# PLL.net
KiCad netlist of a schematic drawn in Altium Designer
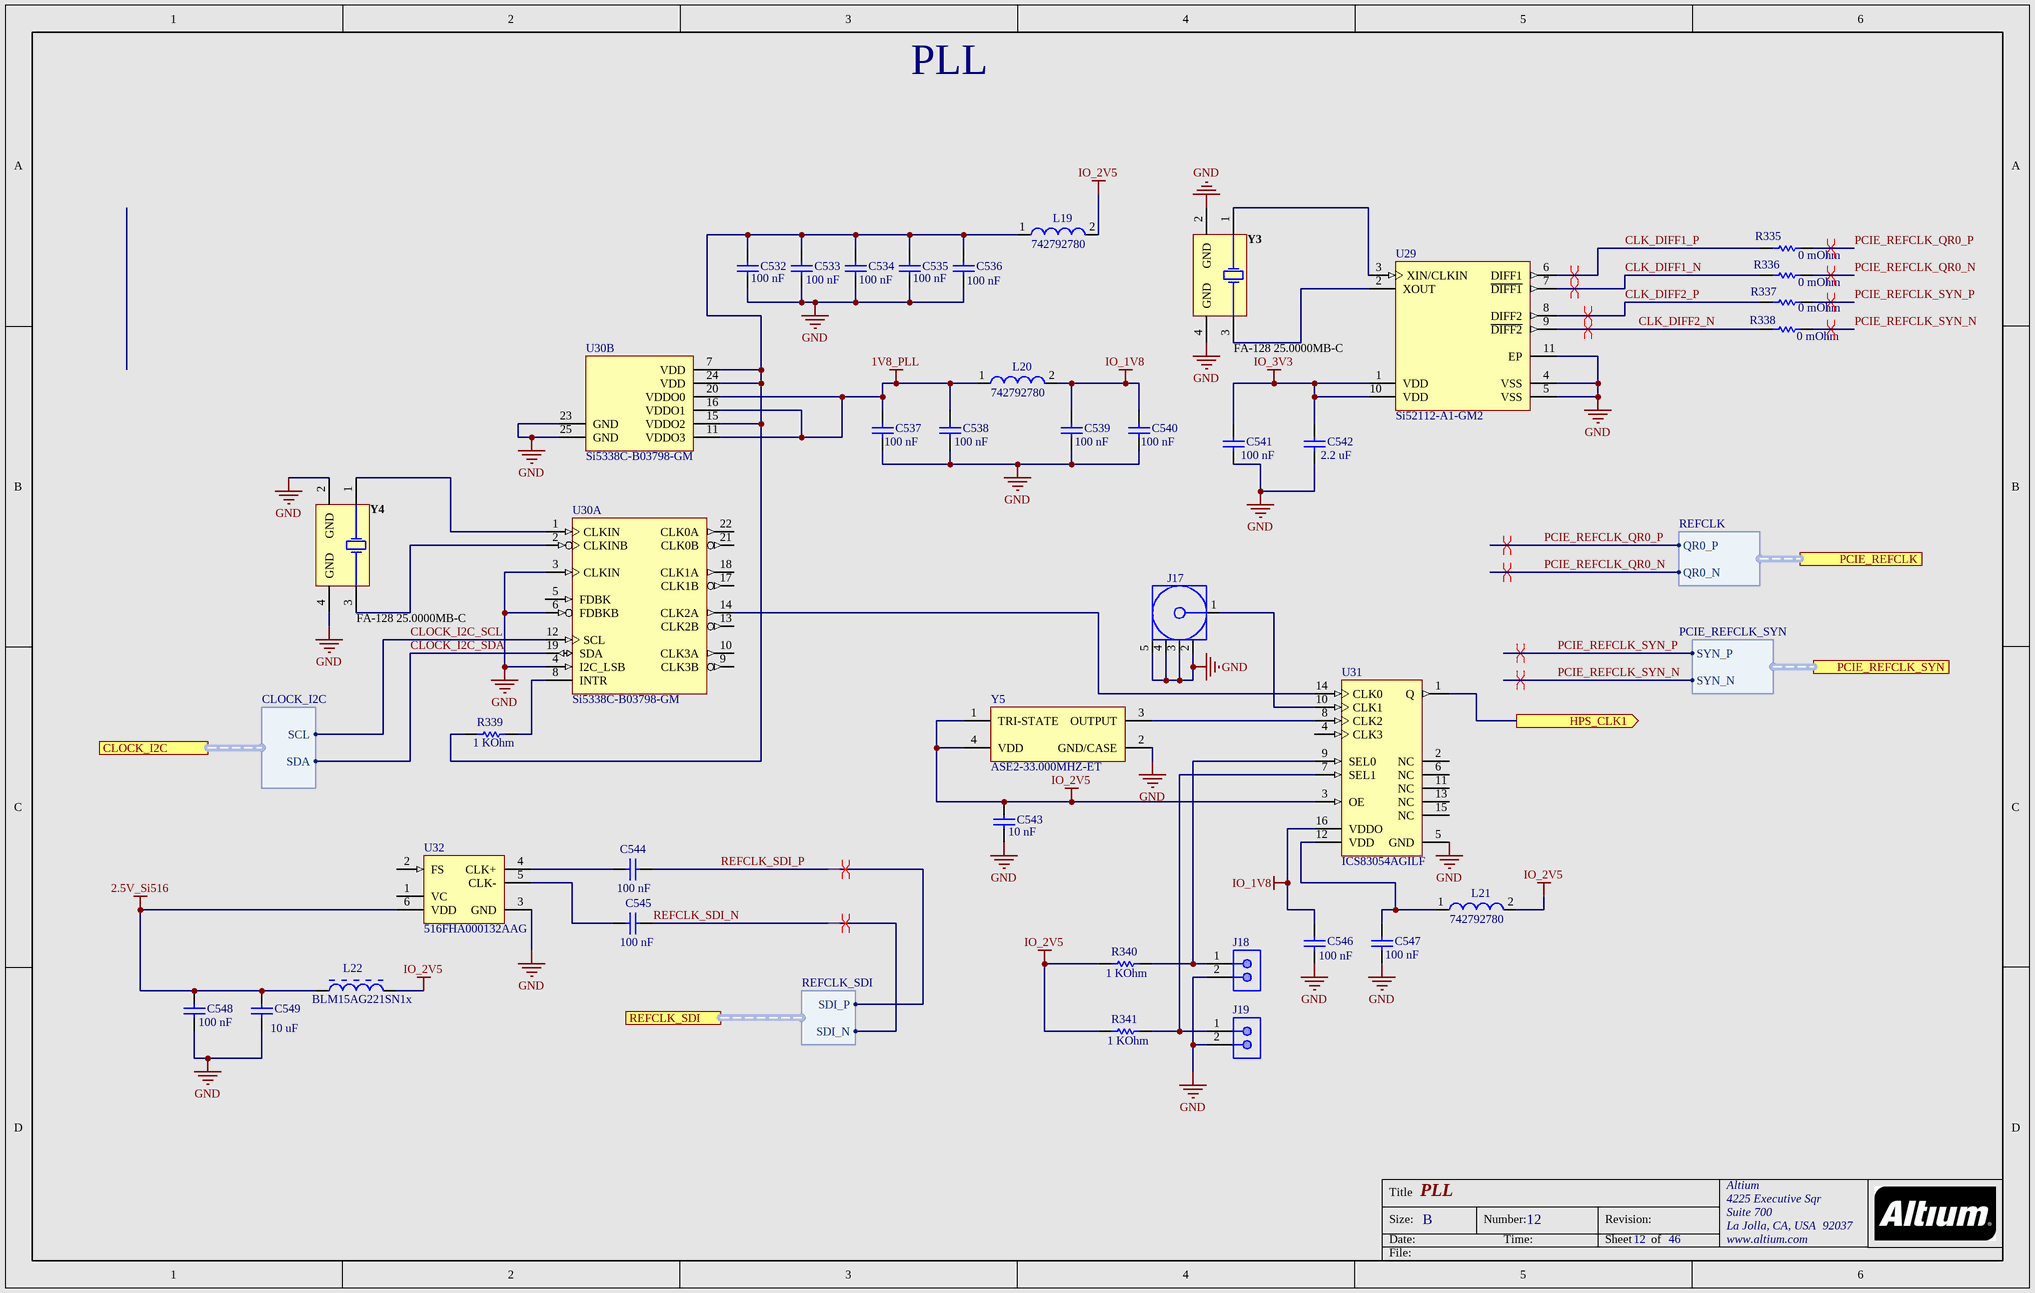
[diagram p0: PLL.SchDoc]

(export (version "E")
  (design (tool "Eeschema 10.0.6"))
  (components
    (comp (ref "C532")
      (value "C1005X7R1E104M")
      (footprint "CAPC1005X55X10LL05")
      (description "Chip Capacitor, 0.1 uF, +/- 20%, 25 V, -55 to 125 degC, 0402 (1005 Metric), RoHS, Tape and Reel")
      (fields (field (name "TOLERANCE") "20%") (field (name "CAPACITANCE") "100 nF"))
      (libsource (lib "Altium Content Vault") (part "CAP-NP-2"))
    )
    (comp (ref "C533")
      (value "C1005X7R1E104M")
      (footprint "CAPC1005X55X10LL05")
      (description "Chip Capacitor, 0.1 uF, +/- 20%, 25 V, -55 to 125 degC, 0402 (1005 Metric), RoHS, Tape and Reel")
      (fields (field (name "TOLERANCE") "20%") (field (name "CAPACITANCE") "100 nF"))
      (libsource (lib "Altium Content Vault") (part "CAP-NP-2"))
    )
    (comp (ref "C534")
      (value "C1005X7R1E104M")
      (footprint "CAPC1005X55X10LL05")
      (description "Chip Capacitor, 0.1 uF, +/- 20%, 25 V, -55 to 125 degC, 0402 (1005 Metric), RoHS, Tape and Reel")
      (fields (field (name "TOLERANCE") "20%") (field (name "CAPACITANCE") "100 nF"))
      (libsource (lib "Altium Content Vault") (part "CAP-NP-2"))
    )
    (comp (ref "C535")
      (value "C1005X7R1E104M")
      (footprint "CAPC1005X55X10LL05")
      (description "Chip Capacitor, 0.1 uF, +/- 20%, 25 V, -55 to 125 degC, 0402 (1005 Metric), RoHS, Tape and Reel")
      (fields (field (name "TOLERANCE") "20%") (field (name "CAPACITANCE") "100 nF"))
      (libsource (lib "Altium Content Vault") (part "CAP-NP-2"))
    )
    (comp (ref "C536")
      (value "C1005X7R1E104M")
      (footprint "CAPC1005X55X10LL05")
      (description "Chip Capacitor, 0.1 uF, +/- 20%, 25 V, -55 to 125 degC, 0402 (1005 Metric), RoHS, Tape and Reel")
      (fields (field (name "TOLERANCE") "20%") (field (name "CAPACITANCE") "100 nF"))
      (libsource (lib "Altium Content Vault") (part "CAP-NP-2"))
    )
    (comp (ref "C537")
      (value "C1005X7R1E104M")
      (footprint "CAPC1005X55X10LL05")
      (description "Chip Capacitor, 0.1 uF, +/- 20%, 25 V, -55 to 125 degC, 0402 (1005 Metric), RoHS, Tape and Reel")
      (fields (field (name "TOLERANCE") "20%") (field (name "CAPACITANCE") "100 nF"))
      (libsource (lib "Altium Content Vault") (part "CAP-NP-2"))
    )
    (comp (ref "C538")
      (value "C1005X7R1E104M")
      (footprint "CAPC1005X55X10LL05")
      (description "Chip Capacitor, 0.1 uF, +/- 20%, 25 V, -55 to 125 degC, 0402 (1005 Metric), RoHS, Tape and Reel")
      (fields (field (name "TOLERANCE") "20%") (field (name "CAPACITANCE") "100 nF"))
      (libsource (lib "Altium Content Vault") (part "CAP-NP-2"))
    )
    (comp (ref "C539")
      (value "C1005X7R1E104M")
      (footprint "CAPC1005X55X10LL05")
      (description "Chip Capacitor, 0.1 uF, +/- 20%, 25 V, -55 to 125 degC, 0402 (1005 Metric), RoHS, Tape and Reel")
      (fields (field (name "TOLERANCE") "20%") (field (name "CAPACITANCE") "100 nF"))
      (libsource (lib "Altium Content Vault") (part "CAP-NP-2"))
    )
    (comp (ref "C540")
      (value "C1005X7R1E104M")
      (footprint "CAPC1005X55X10LL05")
      (description "Chip Capacitor, 0.1 uF, +/- 20%, 25 V, -55 to 125 degC, 0402 (1005 Metric), RoHS, Tape and Reel")
      (fields (field (name "TOLERANCE") "20%") (field (name "CAPACITANCE") "100 nF"))
      (libsource (lib "Altium Content Vault") (part "CAP-NP-2"))
    )
    (comp (ref "C541")
      (value "C1005X7R1E104M")
      (footprint "CAPC1005X55X10LL05")
      (description "Chip Capacitor, 0.1 uF, +/- 20%, 25 V, -55 to 125 degC, 0402 (1005 Metric), RoHS, Tape and Reel")
      (fields (field (name "TOLERANCE") "20%") (field (name "CAPACITANCE") "100 nF"))
      (libsource (lib "Altium Content Vault") (part "CAP-NP-2"))
    )
    (comp (ref "C542")
      (value "GRM188R61A225KE34x")
      (footprint "CAPC1608X90X35ML10T15")
      (description "Chip Capacitor, 2.2 uF, +/- 10%, 10 V, -55 to 85 degC, 0603 (1608 Metric), RoHS, Tape and Reel")
      (fields (field (name "TOLERANCE") "10%") (field (name "CAPACITANCE") "2.2 uF"))
      (libsource (lib "") (part "CAP-NP-2_1"))
    )
    (comp (ref "C543")
      (value "GRM155R71H103KA88D")
      (footprint "CAPC1005X55X25ML05T10")
      (description "Chip Capacitor, 10 nF, +/- 10%, 50 V, -55 to 125 degC, 0402 (1005 Metric), RoHS, Tape and Reel")
      (fields
        (field (name "TOLERANCE") "10%")
        (field (name "CAPACITANCE") "10 nF")
        (field (name "MANUFACTURER") "Basic Passives")
      )
      (libsource (lib "Altium Content Vault") (part "CAP-NP-2"))
    )
    (comp (ref "C544")
      (value "C1005X7R1E104M")
      (footprint "CAPC1005X55X10LL05")
      (description "Chip Capacitor, 0.1 uF, +/- 20%, 25 V, -55 to 125 degC, 0402 (1005 Metric), RoHS, Tape and Reel")
      (fields (field (name "TOLERANCE") "20%") (field (name "CAPACITANCE") "100 nF"))
      (libsource (lib "Altium Content Vault") (part "CAP-NP-2"))
    )
    (comp (ref "C545")
      (value "C1005X7R1E104M")
      (footprint "CAPC1005X55X10LL05")
      (description "Chip Capacitor, 0.1 uF, +/- 20%, 25 V, -55 to 125 degC, 0402 (1005 Metric), RoHS, Tape and Reel")
      (fields (field (name "TOLERANCE") "20%") (field (name "CAPACITANCE") "100 nF"))
      (libsource (lib "Altium Content Vault") (part "CAP-NP-2"))
    )
    (comp (ref "C546")
      (value "C1005X7R1E104M")
      (footprint "CAPC1005X55X10LL05")
      (description "Chip Capacitor, 0.1 uF, +/- 20%, 25 V, -55 to 125 degC, 0402 (1005 Metric), RoHS, Tape and Reel")
      (fields (field (name "TOLERANCE") "20%") (field (name "CAPACITANCE") "100 nF"))
      (libsource (lib "Altium Content Vault") (part "CAP-NP-2"))
    )
    (comp (ref "C547")
      (value "C1005X7R1E104M")
      (footprint "CAPC1005X55X10LL05")
      (description "Chip Capacitor, 0.1 uF, +/- 20%, 25 V, -55 to 125 degC, 0402 (1005 Metric), RoHS, Tape and Reel")
      (fields (field (name "TOLERANCE") "20%") (field (name "CAPACITANCE") "100 nF"))
      (libsource (lib "Altium Content Vault") (part "CAP-NP-2"))
    )
    (comp (ref "C548")
      (value "C1005X7R1E104M")
      (footprint "CAPC1005X55X10LL05")
      (description "Chip Capacitor, 0.1 uF, +/- 20%, 25 V, -55 to 125 degC, 0402 (1005 Metric), RoHS, Tape and Reel")
      (fields (field (name "TOLERANCE") "20%") (field (name "CAPACITANCE") "100 nF"))
      (libsource (lib "Altium Content Vault") (part "CAP-NP-2"))
    )
    (comp (ref "C549")
      (value "C2012X5R1C106K085AC")
      (footprint "CAPC2013X100X20NL20")
      (description "Chip Capacitor, 10 uF, +/- 10%, 16 V, -55 to 85 degC, 0805 (2012 Metric), RoHS, Tape and Reel")
      (fields (field (name "TOLERANCE") "10%") (field (name "CAPACITANCE") "10 uF"))
      (libsource (lib "") (part "CAP-NP-2_1"))
    )
    (comp (ref "J17")
      (value "LTI-SASF54GT")
      (footprint "LHT-LTI-SASF54GT_V")
      (description "SMA Connector, Pitch 2.54 mm, 1 Position, Height 9.5 mm, Tail Length 4 mm, RoHS")
      (fields (field (name "MANUFACTURER") "Lighthorse Technologies Inc."))
      (libsource (lib "Altium Content Vault") (part "CMP-1713-00001-1"))
    )
    (comp (ref "J18")
      (value "613 002 111 21")
      (footprint "WE-61300211121_V")
      (fields (field (name "MANUFACTURER") "Wuerth Elektronik"))
      (libsource (lib "Altium Content Vault") (part "CMP-1712-00002-1"))
    )
    (comp (ref "J19")
      (value "613 002 111 21")
      (footprint "WE-61300211121_V")
      (fields (field (name "MANUFACTURER") "Wuerth Elektronik"))
      (libsource (lib "Altium Content Vault") (part "CMP-1712-00002-1"))
    )
    (comp (ref "L19")
      (value "742792780")
      (footprint "SMD-0402")
      (description "SMD EMI Suppression Ferrite Bead WE-CBF, Z = 220 Ohm")
      (libsource (lib "Altium Content Vault") (part "PAS-IND-INDUCTOR-2"))
    )
    (comp (ref "L20")
      (value "742792780")
      (footprint "SMD-0402")
      (description "SMD EMI Suppression Ferrite Bead WE-CBF, Z = 220 Ohm")
      (libsource (lib "Altium Content Vault") (part "CMP-0220-00137-1"))
    )
    (comp (ref "L21")
      (value "742792780")
      (footprint "SMD-0402")
      (description "SMD EMI Suppression Ferrite Bead WE-CBF, Z = 220 Ohm")
      (libsource (lib "Altium Content Vault") (part "CMP-0220-00137-1"))
    )
    (comp (ref "L22")
      (value "BLM15AG221SN1x")
      (footprint "MURA-BLM15AG221SN1x_V")
      (description "Chip Bead, 220 Ohm, +/- 25 %, 100 MHz, 300 mA, -55 to 125 degC, 0402 (1005 Metric), RoHS")
      (fields (field (name "TOLERANCE") "25%"))
      (libsource (lib "Altium Content Vault") (part "BEAD-2"))
    )
    (comp (ref "R335")
      (value "ERJ-2GE0R00X")
      (footprint "RESC1005X40X25ML05T05")
      (description "Chip Resistor, 0 mOhm, +/- 5%, 100 mW, -55 to 155 degC, 0402 (1005 Metric), RoHS, Tape and Reel")
      (fields
        (field (name "TOLERANCE") "5%")
        (field (name "RESISTANCE") "0 mOhm")
        (field (name "MANUFACTURER") "Basic Passives")
      )
      (libsource (lib "Altium Content Vault") (part "RES-2"))
    )
    (comp (ref "R336")
      (value "ERJ-2GE0R00X")
      (footprint "RESC1005X40X25ML05T05")
      (description "Chip Resistor, 0 mOhm, +/- 5%, 100 mW, -55 to 155 degC, 0402 (1005 Metric), RoHS, Tape and Reel")
      (fields
        (field (name "TOLERANCE") "5%")
        (field (name "RESISTANCE") "0 mOhm")
        (field (name "MANUFACTURER") "Basic Passives")
      )
      (libsource (lib "Altium Content Vault") (part "RES-2"))
    )
    (comp (ref "R337")
      (value "ERJ-2GE0R00X")
      (footprint "RESC1005X40X25ML05T05")
      (description "Chip Resistor, 0 mOhm, +/- 5%, 100 mW, -55 to 155 degC, 0402 (1005 Metric), RoHS, Tape and Reel")
      (fields
        (field (name "TOLERANCE") "5%")
        (field (name "RESISTANCE") "0 mOhm")
        (field (name "MANUFACTURER") "Basic Passives")
      )
      (libsource (lib "Altium Content Vault") (part "RES-2"))
    )
    (comp (ref "R338")
      (value "ERJ-2GE0R00X")
      (footprint "RESC1005X40X25ML05T05")
      (description "Chip Resistor, 0 mOhm, +/- 5%, 100 mW, -55 to 155 degC, 0402 (1005 Metric), RoHS, Tape and Reel")
      (fields
        (field (name "TOLERANCE") "5%")
        (field (name "RESISTANCE") "0 mOhm")
        (field (name "MANUFACTURER") "Basic Passives")
      )
      (libsource (lib "Altium Content Vault") (part "RES-2"))
    )
    (comp (ref "R339")
      (value "ERJ-2RKF1001X")
      (footprint "RESC1005X40X25LL05T05")
      (description "Chip Resistor, 1 KOhm, +/- 1%, 100 mW, -55 to 155 degC, 0402 (1005 Metric), RoHS, Tape and Reel")
      (fields
        (field (name "RESISTANCE") "1 KOhm")
        (field (name "TOLERANCE") "1%")
        (field (name "MANUFACTURER") "Basic Passives")
      )
      (libsource (lib "Altium Content Vault") (part "RES-2"))
    )
    (comp (ref "R340")
      (value "ERJ-2RKF1001X")
      (footprint "RESC1005X40X25LL05T05")
      (description "Chip Resistor, 1 KOhm, +/- 1%, 100 mW, -55 to 155 degC, 0402 (1005 Metric), RoHS, Tape and Reel")
      (fields
        (field (name "RESISTANCE") "1 KOhm")
        (field (name "TOLERANCE") "1%")
        (field (name "MANUFACTURER") "Basic Passives")
      )
      (libsource (lib "Altium Content Vault") (part "RES-2"))
    )
    (comp (ref "R341")
      (value "ERJ-2RKF1001X")
      (footprint "RESC1005X40X25LL05T05")
      (description "Chip Resistor, 1 KOhm, +/- 1%, 100 mW, -55 to 155 degC, 0402 (1005 Metric), RoHS, Tape and Reel")
      (fields
        (field (name "RESISTANCE") "1 KOhm")
        (field (name "TOLERANCE") "1%")
        (field (name "MANUFACTURER") "Basic Passives")
      )
      (libsource (lib "Altium Content Vault") (part "RES-2"))
    )
    (comp (ref "U29")
      (value "Si52112-A1-GM2")
      (footprint "SLAB-TDFN-10_L")
      (fields (field (name "MANUFACTURER") "Silicon Labs"))
      (libsource (lib "Altium Content Vault") (part "CMP-1706-00007-1"))
    )
    (comp (ref "U30")
      (value "Si5338C-B03798-GM")
      (footprint "SLAB-QFN-24-2550x2550TP_V")
      (fields (field (name "MANUFACTURER") "Silicon Labs"))
      (libsource (lib "") (part "CMP-1706-00005-1_1"))
    )
    (comp (ref "U31")
      (value "ICS83054AGILF")
      (footprint "IDT-TSSOP-16_M")
      (description "Single-Ended Multiplexer, 2.375 to 3.465 V, -40 to 85 degC, 16-Pin TSSOP, RoHS, Tube")
      (fields (field (name "MANUFACTURER") "IDT"))
      (libsource (lib "Altium Content Vault") (part "CMP-1699-00001-1"))
    )
    (comp (ref "U32")
      (value "516FHA000132AAG")
      (footprint "SLAB-DFN-6-5000X7000DE_A_V")
      (fields (field (name "MANUFACTURER") "Silicon Labs"))
      (libsource (lib "Altium Content Vault") (part "CMP-1706-00001-1"))
    )
    (comp (ref "Y3")
      (value "FA-128 25.0000MB-C")
      (footprint "EPSON-FA-128_V")
      (description "Range Crystal Unit, 25 MHz, -40 to 85 degC, 4-Pin SMD, RoHS, Tape and Reel")
      (libsource (lib "Altium Content Vault") (part "XTAL-1-3-4"))
    )
    (comp (ref "Y4")
      (value "FA-128 25.0000MB-C")
      (footprint "EPSON-FA-128_V")
      (description "Range Crystal Unit, 25 MHz, -40 to 85 degC, 4-Pin SMD, RoHS, Tape and Reel")
      (libsource (lib "Altium Content Vault") (part "XTAL-1-3-4"))
    )
    (comp (ref "Y5")
      (value "ASE2-33.000MHZ-ET")
      (footprint "ABRA-ASE2_V")
      (fields (field (name "MANUFACTURER") "Abracon"))
      (libsource (lib "Altium Content Vault") (part "CMP-1688-00001-1"))
    )
  )
  (nets
    (net (code "5") (name "/CLK_DIFF1_N") (class "Default")
      (node (ref "R336") (pin "1") (pinfunction "1_1") (pintype "passive"))
      (node (ref "U29") (pin "7") (pinfunction "~{DIFF1}_7") (pintype "output"))
    )
    (net (code "6") (name "/CLK_DIFF1_P") (class "Default")
      (node (ref "R335") (pin "1") (pinfunction "1_1") (pintype "passive"))
      (node (ref "U29") (pin "6") (pinfunction "DIFF1_6") (pintype "output"))
    )
    (net (code "7") (name "/CLK_DIFF2_N") (class "Default")
      (node (ref "R338") (pin "1") (pinfunction "1_1") (pintype "passive"))
      (node (ref "U29") (pin "9") (pinfunction "~{DIFF2}_9") (pintype "output"))
    )
    (net (code "8") (name "/CLK_DIFF2_P") (class "Default")
      (node (ref "R337") (pin "1") (pinfunction "1_1") (pintype "passive"))
      (node (ref "U29") (pin "8") (pinfunction "DIFF2_8") (pintype "output"))
    )
    (net (code "9") (name "/CLOCK_I2C_SCL") (class "Default")
      (node (ref "U30") (pin "12") (pinfunction "SCL_12") (pintype "input"))
    )
    (net (code "10") (name "/CLOCK_I2C_SDA") (class "Default")
      (node (ref "U30") (pin "19") (pinfunction "SDA_19") (pintype "bidirectional"))
    )
    (net (code "11") (name "/HPS_CLK1") (class "Default")
      (node (ref "U31") (pin "1") (pinfunction "Q_1") (pintype "output"))
    )
    (net (code "12") (name "/PCIE_REFCLK_QR0_N") (class "Default")
      (node (ref "R336") (pin "2") (pinfunction "2_2") (pintype "passive"))
    )
    (net (code "13") (name "/PCIE_REFCLK_QR0_P") (class "Default")
      (node (ref "R335") (pin "2") (pinfunction "2_2") (pintype "passive"))
    )
    (net (code "14") (name "/PCIE_REFCLK_SYN_N") (class "Default")
      (node (ref "R338") (pin "2") (pinfunction "2_2") (pintype "passive"))
    )
    (net (code "15") (name "/PCIE_REFCLK_SYN_P") (class "Default")
      (node (ref "R337") (pin "2") (pinfunction "2_2") (pintype "passive"))
    )
    (net (code "16") (name "/REFCLK_SDI_N") (class "Default")
      (node (ref "C545") (pin "1") (pinfunction "1_1") (pintype "passive"))
    )
    (net (code "17") (name "/REFCLK_SDI_P") (class "Default")
      (node (ref "C544") (pin "1") (pinfunction "1_1") (pintype "passive"))
    )
    (net (code "22") (name "1V8_PLL") (class "Default")
      (node (ref "C537") (pin "2") (pinfunction "2_2") (pintype "passive"))
      (node (ref "C538") (pin "2") (pinfunction "2_2") (pintype "passive"))
      (node (ref "L20") (pin "1") (pinfunction "1_1") (pintype "passive"))
      (node (ref "U30") (pin "11") (pinfunction "VDDO3_11") (pintype "power_in"))
      (node (ref "U30") (pin "16") (pinfunction "VDDO1_16") (pintype "power_in"))
      (node (ref "U30") (pin "20") (pinfunction "VDDO0_20") (pintype "power_in"))
    )
    (net (code "23") (name "2.5V_Si516") (class "Default")
      (node (ref "C548") (pin "2") (pinfunction "2_2") (pintype "passive"))
      (node (ref "C549") (pin "2") (pinfunction "2_2") (pintype "passive"))
      (node (ref "L22") (pin "1") (pinfunction "1_1") (pintype "passive"))
      (node (ref "U32") (pin "6") (pinfunction "VDD_6") (pintype "power_in"))
    )
    (net (code "24") (name "GND") (class "Default")
      (node (ref "C532") (pin "1") (pinfunction "1_1") (pintype "passive"))
      (node (ref "C533") (pin "1") (pinfunction "1_1") (pintype "passive"))
      (node (ref "C534") (pin "1") (pinfunction "1_1") (pintype "passive"))
      (node (ref "C535") (pin "1") (pinfunction "1_1") (pintype "passive"))
      (node (ref "C536") (pin "1") (pinfunction "1_1") (pintype "passive"))
      (node (ref "C537") (pin "1") (pinfunction "1_1") (pintype "passive"))
      (node (ref "C538") (pin "1") (pinfunction "1_1") (pintype "passive"))
      (node (ref "C539") (pin "1") (pinfunction "1_1") (pintype "passive"))
      (node (ref "C540") (pin "1") (pinfunction "1_1") (pintype "passive"))
      (node (ref "C541") (pin "1") (pinfunction "1_1") (pintype "passive"))
      (node (ref "C542") (pin "1") (pinfunction "1_1") (pintype "passive"))
      (node (ref "C543") (pin "1") (pinfunction "1_1") (pintype "passive"))
      (node (ref "C546") (pin "1") (pinfunction "1_1") (pintype "passive"))
      (node (ref "C547") (pin "1") (pinfunction "1_1") (pintype "passive"))
      (node (ref "C548") (pin "1") (pinfunction "1_1") (pintype "passive"))
      (node (ref "C549") (pin "1") (pinfunction "1_1") (pintype "passive"))
      (node (ref "J17") (pin "2") (pinfunction "2_2") (pintype "passive"))
      (node (ref "J17") (pin "3") (pinfunction "3_3") (pintype "passive"))
      (node (ref "J17") (pin "4") (pinfunction "4_4") (pintype "passive"))
      (node (ref "J17") (pin "5") (pinfunction "5_5") (pintype "passive"))
      (node (ref "J18") (pin "2") (pinfunction "2_2") (pintype "passive"))
      (node (ref "J19") (pin "2") (pinfunction "2_2") (pintype "passive"))
      (node (ref "U29") (pin "11") (pinfunction "EP_11") (pintype "passive"))
      (node (ref "U29") (pin "4") (pinfunction "VSS_4") (pintype "power_in"))
      (node (ref "U29") (pin "5") (pinfunction "VSS_5") (pintype "power_in"))
      (node (ref "U30") (pin "23") (pinfunction "GND_23") (pintype "power_in"))
      (node (ref "U30") (pin "25") (pinfunction "GND_25") (pintype "power_in"))
      (node (ref "U30") (pin "3") (pinfunction "CLKIN_3") (pintype "input"))
      (node (ref "U30") (pin "4") (pinfunction "I2C_LSB_4") (pintype "input"))
      (node (ref "U30") (pin "6") (pinfunction "FDBKB_6") (pintype "input"))
      (node (ref "U31") (pin "5") (pinfunction "GND_5") (pintype "power_in"))
      (node (ref "U32") (pin "3") (pinfunction "GND_3") (pintype "power_in"))
      (node (ref "Y3") (pin "2") (pinfunction "GND_2") (pintype "power_in"))
      (node (ref "Y3") (pin "4") (pinfunction "GND_4") (pintype "power_in"))
      (node (ref "Y4") (pin "2") (pinfunction "GND_2") (pintype "power_in"))
      (node (ref "Y4") (pin "4") (pinfunction "GND_4") (pintype "power_in"))
      (node (ref "Y5") (pin "2") (pinfunction "GND/CASE_2") (pintype "power_in"))
    )
    (net (code "25") (name "IO_1V8") (class "Default")
      (node (ref "C539") (pin "2") (pinfunction "2_2") (pintype "passive"))
      (node (ref "C540") (pin "2") (pinfunction "2_2") (pintype "passive"))
      (node (ref "C546") (pin "2") (pinfunction "2_2") (pintype "passive"))
      (node (ref "L20") (pin "2") (pinfunction "2_2") (pintype "passive"))
      (node (ref "U31") (pin "16") (pinfunction "VDDO_16") (pintype "power_in"))
    )
    (net (code "26") (name "IO_2V5") (class "Default")
      (node (ref "C543") (pin "2") (pinfunction "2_2") (pintype "passive"))
      (node (ref "L19") (pin "2") (pinfunction "2_2") (pintype "passive"))
      (node (ref "L21") (pin "2") (pinfunction "2_2") (pintype "passive"))
      (node (ref "L22") (pin "2") (pinfunction "2_2") (pintype "passive"))
      (node (ref "R340") (pin "1") (pinfunction "1_1") (pintype "passive"))
      (node (ref "R341") (pin "1") (pinfunction "1_1") (pintype "passive"))
      (node (ref "U31") (pin "3") (pinfunction "OE_3") (pintype "input"))
      (node (ref "Y5") (pin "1") (pinfunction "TRI-STATE_1") (pintype "passive"))
      (node (ref "Y5") (pin "4") (pinfunction "VDD_4") (pintype "power_in"))
    )
    (net (code "27") (name "IO_3V3") (class "Default")
      (node (ref "C541") (pin "2") (pinfunction "2_2") (pintype "passive"))
      (node (ref "C542") (pin "2") (pinfunction "2_2") (pintype "passive"))
      (node (ref "U29") (pin "1") (pinfunction "VDD_1") (pintype "power_in"))
      (node (ref "U29") (pin "10") (pinfunction "VDD_10") (pintype "power_in"))
    )
    (net (code "28") (name "Net-(U29-XIN{slash}CLKIN)") (class "Default")
      (node (ref "U29") (pin "3") (pinfunction "XIN/CLKIN_3") (pintype "input"))
      (node (ref "Y3") (pin "1") (pinfunction "X1_1") (pintype "passive"))
    )
    (net (code "29") (name "Net-(U29-XOUT)") (class "Default")
      (node (ref "U29") (pin "2") (pinfunction "XOUT_2") (pintype "passive"))
      (node (ref "Y3") (pin "3") (pinfunction "X2_3") (pintype "passive"))
    )
    (net (code "30") (name "Net-(U30A-CLK2A)") (class "Default")
      (node (ref "U30") (pin "14") (pinfunction "CLK2A_14") (pintype "output"))
      (node (ref "U31") (pin "14") (pinfunction "CLK0_14") (pintype "input"))
    )
    (net (code "31") (name "Net-(U30A-CLKINB)") (class "Default")
      (node (ref "U30") (pin "2") (pinfunction "CLKINB_2") (pintype "input"))
      (node (ref "Y4") (pin "3") (pinfunction "X2_3") (pintype "passive"))
    )
    (net (code "32") (name "Net-(U30A-INTR)") (class "Default")
      (node (ref "R339") (pin "2") (pinfunction "2_2") (pintype "passive"))
      (node (ref "U30") (pin "8") (pinfunction "INTR_8") (pintype "open_collector"))
    )
    (net (code "33") (name "Net-(U30B-VDDO2)") (class "Default")
      (node (ref "C532") (pin "2") (pinfunction "2_2") (pintype "passive"))
      (node (ref "C533") (pin "2") (pinfunction "2_2") (pintype "passive"))
      (node (ref "C534") (pin "2") (pinfunction "2_2") (pintype "passive"))
      (node (ref "C535") (pin "2") (pinfunction "2_2") (pintype "passive"))
      (node (ref "C536") (pin "2") (pinfunction "2_2") (pintype "passive"))
      (node (ref "L19") (pin "1") (pinfunction "1_1") (pintype "passive"))
      (node (ref "R339") (pin "1") (pinfunction "1_1") (pintype "passive"))
      (node (ref "U30") (pin "15") (pinfunction "VDDO2_15") (pintype "power_in"))
      (node (ref "U30") (pin "24") (pinfunction "VDD_24") (pintype "power_in"))
      (node (ref "U30") (pin "7") (pinfunction "VDD_7") (pintype "power_in"))
    )
    (net (code "34") (name "Net-(U31-CLK1)") (class "Default")
      (node (ref "J17") (pin "1") (pinfunction "1_1") (pintype "passive"))
      (node (ref "U31") (pin "10") (pinfunction "CLK1_10") (pintype "input"))
    )
    (net (code "35") (name "Net-(U31-CLK2)") (class "Default")
      (node (ref "U31") (pin "8") (pinfunction "CLK2_8") (pintype "input"))
      (node (ref "Y5") (pin "3") (pinfunction "OUTPUT_3") (pintype "passive"))
    )
    (net (code "36") (name "Net-(U31-SEL0)") (class "Default")
      (node (ref "J18") (pin "1") (pinfunction "1_1") (pintype "passive"))
      (node (ref "R340") (pin "2") (pinfunction "2_2") (pintype "passive"))
      (node (ref "U31") (pin "9") (pinfunction "SEL0_9") (pintype "input"))
    )
    (net (code "37") (name "Net-(U31-SEL1)") (class "Default")
      (node (ref "J19") (pin "1") (pinfunction "1_1") (pintype "passive"))
      (node (ref "R341") (pin "2") (pinfunction "2_2") (pintype "passive"))
      (node (ref "U31") (pin "7") (pinfunction "SEL1_7") (pintype "input"))
    )
    (net (code "38") (name "Net-(U31-VDD)") (class "Default")
      (node (ref "C547") (pin "2") (pinfunction "2_2") (pintype "passive"))
      (node (ref "L21") (pin "1") (pinfunction "1_1") (pintype "passive"))
      (node (ref "U31") (pin "12") (pinfunction "VDD_12") (pintype "power_in"))
    )
    (net (code "39") (name "Net-(U32-CLK+)") (class "Default")
      (node (ref "C544") (pin "2") (pinfunction "2_2") (pintype "passive"))
      (node (ref "U32") (pin "4") (pinfunction "CLK+_4") (pintype "tri_state"))
    )
    (net (code "40") (name "Net-(U32-CLK-)") (class "Default")
      (node (ref "C545") (pin "2") (pinfunction "2_2") (pintype "passive"))
      (node (ref "U32") (pin "5") (pinfunction "CLK-_5") (pintype "tri_state"))
    )
    (net (code "41") (name "Net-(Y4-X1)") (class "Default")
      (node (ref "U30") (pin "1") (pinfunction "CLKIN_1") (pintype "input"))
      (node (ref "Y4") (pin "1") (pinfunction "X1_1") (pintype "passive"))
    )
    (net (code "42") (name "unconnected-(U30A-CLK0A-Pad22)") (class "Default")
      (node (ref "U30") (pin "22") (pinfunction "CLK0A_22") (pintype "output"))
    )
    (net (code "43") (name "unconnected-(U30A-CLK0B-Pad21)") (class "Default")
      (node (ref "U30") (pin "21") (pinfunction "CLK0B_21") (pintype "output"))
    )
    (net (code "44") (name "unconnected-(U30A-CLK1A-Pad18)") (class "Default")
      (node (ref "U30") (pin "18") (pinfunction "CLK1A_18") (pintype "output"))
    )
    (net (code "45") (name "unconnected-(U30A-CLK1B-Pad17)") (class "Default")
      (node (ref "U30") (pin "17") (pinfunction "CLK1B_17") (pintype "output"))
    )
    (net (code "46") (name "unconnected-(U30A-CLK2B-Pad13)") (class "Default")
      (node (ref "U30") (pin "13") (pinfunction "CLK2B_13") (pintype "output"))
    )
    (net (code "47") (name "unconnected-(U30A-CLK3A-Pad10)") (class "Default")
      (node (ref "U30") (pin "10") (pinfunction "CLK3A_10") (pintype "output"))
    )
    (net (code "48") (name "unconnected-(U30A-CLK3B-Pad9)") (class "Default")
      (node (ref "U30") (pin "9") (pinfunction "CLK3B_9") (pintype "output"))
    )
    (net (code "49") (name "unconnected-(U30A-FDBK-Pad5)") (class "Default")
      (node (ref "U30") (pin "5") (pinfunction "FDBK_5") (pintype "input"))
    )
    (net (code "50") (name "unconnected-(U31-CLK3-Pad4)") (class "Default")
      (node (ref "U31") (pin "4") (pinfunction "CLK3_4") (pintype "input"))
    )
    (net (code "51") (name "unconnected-(U31-NC-Pad2)") (class "Default")
      (node (ref "U31") (pin "2") (pinfunction "NC_2") (pintype "passive"))
    )
    (net (code "52") (name "unconnected-(U31-NC-Pad6)") (class "Default")
      (node (ref "U31") (pin "6") (pinfunction "NC_6") (pintype "passive"))
    )
    (net (code "53") (name "unconnected-(U31-NC-Pad11)") (class "Default")
      (node (ref "U31") (pin "11") (pinfunction "NC_11") (pintype "passive"))
    )
    (net (code "54") (name "unconnected-(U31-NC-Pad13)") (class "Default")
      (node (ref "U31") (pin "13") (pinfunction "NC_13") (pintype "passive"))
    )
    (net (code "55") (name "unconnected-(U31-NC-Pad15)") (class "Default")
      (node (ref "U31") (pin "15") (pinfunction "NC_15") (pintype "passive"))
    )
    (net (code "56") (name "unconnected-(U32-FS-Pad2)") (class "Default")
      (node (ref "U32") (pin "2") (pinfunction "FS_2") (pintype "input"))
    )
    (net (code "57") (name "unconnected-(U32-VC-Pad1)") (class "Default")
      (node (ref "U32") (pin "1") (pinfunction "VC_1") (pintype "power_in"))
    )
  )
)
